# Power.net
KiCad netlist of a schematic drawn in Altium Designer
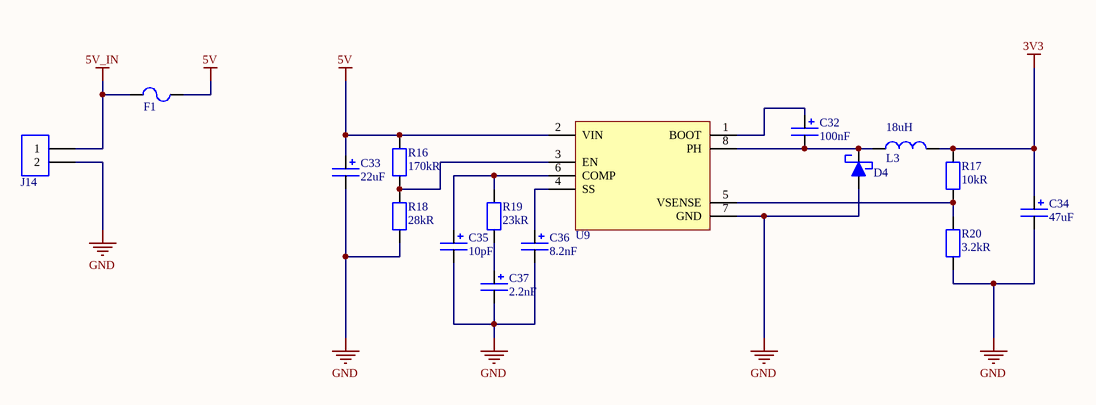
[diagram p0: Power.SchDoc]

(export (version "E")
  (design (tool "Eeschema 10.0.6"))
  (components
    (comp (ref "C32")
      (value "100nF")
      (footprint "CAP 0603")
      (description "Multilayer Ceramic Capacitor")
      (fields (field (name "Comment") "CAP 0603"))
      (libsource (lib "Kaptanyums Lib") (part "CAP 0603"))
    )
    (comp (ref "C33")
      (value "22uF")
      (footprint "CAP 0603")
      (description "Multilayer Ceramic Capacitor")
      (fields (field (name "Comment") "CAP 0603"))
      (libsource (lib "Kaptanyums Lib") (part "CAP 0603"))
    )
    (comp (ref "C34")
      (value "47uF")
      (footprint "CAP 0603")
      (description "Multilayer Ceramic Capacitor")
      (fields (field (name "Comment") "CAP 0603"))
      (libsource (lib "Kaptanyums Lib") (part "CAP 0603"))
    )
    (comp (ref "C35")
      (value "10pF")
      (footprint "CAP 0603")
      (description "Multilayer Ceramic Capacitor")
      (fields (field (name "Comment") "CAP 0603"))
      (libsource (lib "Kaptanyums Lib") (part "CAP 0603"))
    )
    (comp (ref "C36")
      (value "8.2nF")
      (footprint "CAP 0603")
      (description "Multilayer Ceramic Capacitor")
      (fields (field (name "Comment") "CAP 0603"))
      (libsource (lib "Kaptanyums Lib") (part "CAP 0603"))
    )
    (comp (ref "C37")
      (value "2.2nF")
      (footprint "CAP 0603")
      (description "Multilayer Ceramic Capacitor")
      (fields (field (name "Comment") "CAP 0603"))
      (libsource (lib "Kaptanyums Lib") (part "CAP 0603"))
    )
    (comp (ref "D4")
      (value "1N5819HW-7-F")
      (footprint "SOD123")
      (description "Diode Schottky")
      (fields (field (name "VOLTAGE") "40V"))
      (libsource (lib "Kaptanyums Lib") (part "1N5819HW-7-F"))
    )
    (comp (ref "F1")
      (value "PTC 1206")
      (footprint "PTC 1206")
      (description "Fuse")
      (libsource (lib "Kaptanyums Lib") (part "PTC 1206"))
    )
    (comp (ref "J14")
      (value "282845-2")
      (footprint "TERM-21")
      (description "Screw Terminal")
      (libsource (lib "Kaptanyums Lib") (part "TERM-21"))
    )
    (comp (ref "L3")
      (value "18uH")
      (footprint "IND 6X6")
      (description "SMD Inductor")
      (fields (field (name "Comment") "NR6028"))
      (libsource (lib "Kaptanyums Lib") (part "NR6028"))
    )
    (comp (ref "R16")
      (value "170kR")
      (footprint "RESISTOR 0603")
      (description "SMD Chip Resistor")
      (fields (field (name "Comment") "RES 0603"))
      (libsource (lib "Kaptanyums Lib") (part "RES 0603"))
    )
    (comp (ref "R17")
      (value "10kR")
      (footprint "RESISTOR 0603")
      (description "SMD Chip Resistor")
      (fields (field (name "Comment") "RES 0603"))
      (libsource (lib "Kaptanyums Lib") (part "RES 0603"))
    )
    (comp (ref "R18")
      (value "28kR")
      (footprint "RESISTOR 0603")
      (description "SMD Chip Resistor")
      (fields (field (name "Comment") "RES 0603"))
      (libsource (lib "Kaptanyums Lib") (part "RES 0603"))
    )
    (comp (ref "R19")
      (value "23kR")
      (footprint "RESISTOR 0603")
      (description "SMD Chip Resistor")
      (fields (field (name "Comment") "RES 0603"))
      (libsource (lib "Kaptanyums Lib") (part "RES 0603"))
    )
    (comp (ref "R20")
      (value "3.2kR")
      (footprint "RESISTOR 0603")
      (description "SMD Chip Resistor")
      (fields (field (name "Comment") "RES 0603"))
      (libsource (lib "Kaptanyums Lib") (part "RES 0603"))
    )
    (comp (ref "U9")
      (value "TPS54231")
      (footprint "SOIC-8")
      (description "Regulator Switch")
      (libsource (lib "Schlib") (part "TPS54231"))
    )
  )
  (nets
    (net (code "1") (name "3V3") (class "Default")
      (node (ref "C34") (pin "1") (pinfunction "1_1") (pintype "passive"))
      (node (ref "L3") (pin "2") (pinfunction "2_2") (pintype "passive"))
      (node (ref "R17") (pin "2") (pinfunction "2_2") (pintype "passive"))
    )
    (net (code "2") (name "5V") (class "Default")
      (node (ref "C33") (pin "1") (pinfunction "1_1") (pintype "passive"))
      (node (ref "F1") (pin "2") (pinfunction "2_2") (pintype "passive"))
      (node (ref "R16") (pin "2") (pinfunction "2_2") (pintype "passive"))
      (node (ref "U9") (pin "2") (pinfunction "VIN_2") (pintype "passive"))
    )
    (net (code "3") (name "5V_IN") (class "Default")
      (node (ref "F1") (pin "1") (pinfunction "1_1") (pintype "passive"))
      (node (ref "J14") (pin "1") (pinfunction "1_1") (pintype "passive"))
    )
    (net (code "4") (name "GND") (class "Default")
      (node (ref "C33") (pin "2") (pinfunction "2_2") (pintype "passive"))
      (node (ref "C34") (pin "2") (pinfunction "2_2") (pintype "passive"))
      (node (ref "C35") (pin "2") (pinfunction "2_2") (pintype "passive"))
      (node (ref "C36") (pin "2") (pinfunction "2_2") (pintype "passive"))
      (node (ref "C37") (pin "2") (pinfunction "2_2") (pintype "passive"))
      (node (ref "D4") (pin "2") (pinfunction "2_2") (pintype "passive"))
      (node (ref "J14") (pin "2") (pinfunction "2_2") (pintype "passive"))
      (node (ref "R18") (pin "1") (pinfunction "1_1") (pintype "passive"))
      (node (ref "R20") (pin "1") (pinfunction "1_1") (pintype "passive"))
      (node (ref "U9") (pin "7") (pinfunction "GND_7") (pintype "passive"))
    )
    (net (code "5") (name "Net-(C37-Pad1)") (class "Default")
      (node (ref "C37") (pin "1") (pinfunction "1_1") (pintype "passive"))
      (node (ref "R19") (pin "1") (pinfunction "1_1") (pintype "passive"))
    )
    (net (code "6") (name "Net-(U9-BOOT)") (class "Default")
      (node (ref "C32") (pin "1") (pinfunction "1_1") (pintype "passive"))
      (node (ref "U9") (pin "1") (pinfunction "BOOT_1") (pintype "passive"))
    )
    (net (code "7") (name "Net-(U9-COMP)") (class "Default")
      (node (ref "C35") (pin "1") (pinfunction "1_1") (pintype "passive"))
      (node (ref "R19") (pin "2") (pinfunction "2_2") (pintype "passive"))
      (node (ref "U9") (pin "6") (pinfunction "COMP_6") (pintype "passive"))
    )
    (net (code "8") (name "Net-(U9-EN)") (class "Default")
      (node (ref "R16") (pin "1") (pinfunction "1_1") (pintype "passive"))
      (node (ref "R18") (pin "2") (pinfunction "2_2") (pintype "passive"))
      (node (ref "U9") (pin "3") (pinfunction "EN_3") (pintype "passive"))
    )
    (net (code "9") (name "Net-(U9-PH)") (class "Default")
      (node (ref "C32") (pin "2") (pinfunction "2_2") (pintype "passive"))
      (node (ref "D4") (pin "1") (pinfunction "1_1") (pintype "passive"))
      (node (ref "L3") (pin "1") (pinfunction "1_1") (pintype "passive"))
      (node (ref "U9") (pin "8") (pinfunction "PH_8") (pintype "passive"))
    )
    (net (code "10") (name "Net-(U9-SS)") (class "Default")
      (node (ref "C36") (pin "1") (pinfunction "1_1") (pintype "passive"))
      (node (ref "U9") (pin "4") (pinfunction "SS_4") (pintype "passive"))
    )
    (net (code "11") (name "Net-(U9-VSENSE)") (class "Default")
      (node (ref "R17") (pin "1") (pinfunction "1_1") (pintype "passive"))
      (node (ref "R20") (pin "2") (pinfunction "2_2") (pintype "passive"))
      (node (ref "U9") (pin "5") (pinfunction "VSENSE_5") (pintype "passive"))
    )
  )
)
